# RS232_MAX3223.net
KiCad netlist of a schematic drawn in Altium Designer
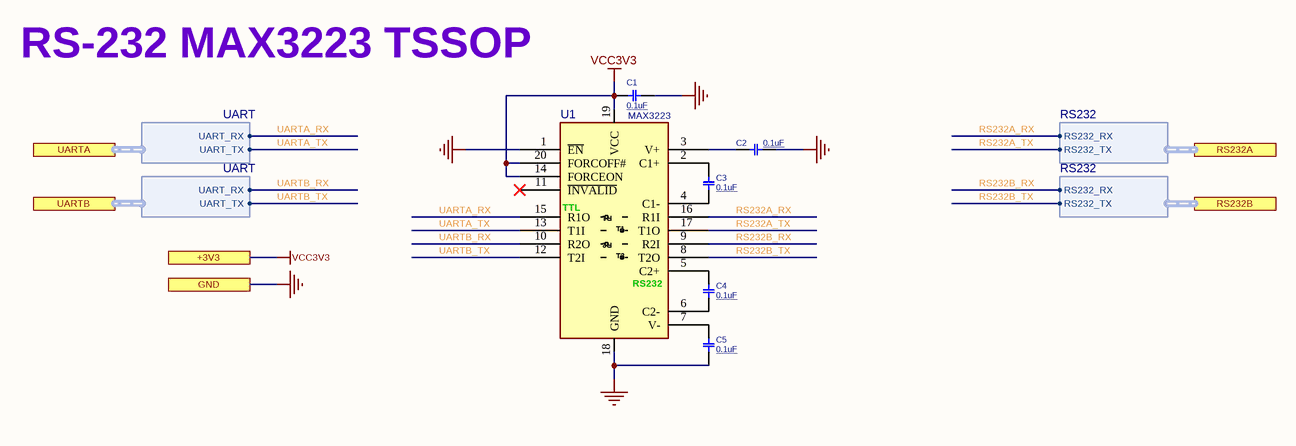
[diagram p0: RS232_MAX3223.SchDoc]

(export (version "E")
  (design (tool "Eeschema 10.0.6"))
  (components
    (comp (ref "C1")
      (value "0.1uF")
      (footprint "C0402")
      (description "CAP, MLCC")
      (fields (field (name "MANF_P#") "MANF_PART#"))
      (libsource (lib "passive_smd") (part "CAP_SMD_MLCC_0402"))
    )
    (comp (ref "C2")
      (value "0.1uF")
      (footprint "C0402")
      (description "CAP, MLCC")
      (fields (field (name "MANF_P#") "MANF_PART#"))
      (libsource (lib "passive_smd") (part "CAP_SMD_MLCC_0402"))
    )
    (comp (ref "C3")
      (value "0.1uF")
      (footprint "C0402")
      (description "CAP, MLCC")
      (fields (field (name "MANF_P#") "MANF_PART#"))
      (libsource (lib "passive_smd") (part "CAP_SMD_MLCC_0402"))
    )
    (comp (ref "C4")
      (value "0.1uF")
      (footprint "C0402")
      (description "CAP, MLCC")
      (fields (field (name "MANF_P#") "MANF_PART#"))
      (libsource (lib "passive_smd") (part "CAP_SMD_MLCC_0402"))
    )
    (comp (ref "C5")
      (value "0.1uF")
      (footprint "C0402")
      (description "CAP, MLCC")
      (fields (field (name "MANF_P#") "MANF_PART#"))
      (libsource (lib "passive_smd") (part "CAP_SMD_MLCC_0402"))
    )
    (comp (ref "U1")
      (value "MAX3223")
      (footprint "SOG65_20_W")
      (description "RS-232, DUAL, +3~5V, Driver/Receiver, Low-Power, up to 1Mbps, Using Four 0.1µF External Capacitor")
      (fields (field (name "MANF") "Maxim Integrated") (field (name "MANF_PART#") "MAX3223ECAP+"))
      (libsource (lib "RASA5") (part "MAX3223_SSOP20W"))
    )
  )
  (nets
    (net (code "3") (name "/RS232A_RX") (class "Default")
      (node (ref "U1") (pin "16") (pinfunction "R1I_16") (pintype "passive"))
    )
    (net (code "4") (name "/RS232A_TX") (class "Default")
      (node (ref "U1") (pin "17") (pinfunction "T1O_17") (pintype "passive"))
    )
    (net (code "5") (name "/RS232B_RX") (class "Default")
      (node (ref "U1") (pin "9") (pinfunction "R2I_9") (pintype "passive"))
    )
    (net (code "6") (name "/RS232B_TX") (class "Default")
      (node (ref "U1") (pin "8") (pinfunction "T2O_8") (pintype "passive"))
    )
    (net (code "7") (name "/UARTA_RX") (class "Default")
      (node (ref "U1") (pin "15") (pinfunction "R1O_15") (pintype "passive"))
    )
    (net (code "8") (name "/UARTA_TX") (class "Default")
      (node (ref "U1") (pin "13") (pinfunction "T1I_13") (pintype "passive"))
    )
    (net (code "9") (name "/UARTB_RX") (class "Default")
      (node (ref "U1") (pin "10") (pinfunction "R2O_10") (pintype "passive"))
    )
    (net (code "10") (name "/UARTB_TX") (class "Default")
      (node (ref "U1") (pin "12") (pinfunction "T2I_12") (pintype "passive"))
    )
    (net (code "13") (name "GND") (class "Default")
      (node (ref "C1") (pin "1") (pinfunction "1_1") (pintype "passive"))
      (node (ref "C2") (pin "2") (pinfunction "2_2") (pintype "passive"))
      (node (ref "C5") (pin "2") (pinfunction "2_2") (pintype "passive"))
      (node (ref "U1") (pin "1") (pinfunction "~{EN}_1") (pintype "passive"))
      (node (ref "U1") (pin "18") (pinfunction "GND_18") (pintype "passive"))
    )
    (net (code "14") (name "Net-(U1-C1+)") (class "Default")
      (node (ref "C3") (pin "1") (pinfunction "1_1") (pintype "passive"))
      (node (ref "U1") (pin "2") (pinfunction "C1+_2") (pintype "passive"))
    )
    (net (code "15") (name "Net-(U1-C1-)") (class "Default")
      (node (ref "C3") (pin "2") (pinfunction "2_2") (pintype "passive"))
      (node (ref "U1") (pin "4") (pinfunction "C1-_4") (pintype "passive"))
    )
    (net (code "16") (name "Net-(U1-C2+)") (class "Default")
      (node (ref "C4") (pin "1") (pinfunction "1_1") (pintype "passive"))
      (node (ref "U1") (pin "5") (pinfunction "C2+_5") (pintype "passive"))
    )
    (net (code "17") (name "Net-(U1-C2-)") (class "Default")
      (node (ref "C4") (pin "2") (pinfunction "2_2") (pintype "passive"))
      (node (ref "U1") (pin "6") (pinfunction "C2-_6") (pintype "passive"))
    )
    (net (code "18") (name "Net-(U1-V+)") (class "Default")
      (node (ref "C2") (pin "1") (pinfunction "1_1") (pintype "passive"))
      (node (ref "U1") (pin "3") (pinfunction "V+_3") (pintype "passive"))
    )
    (net (code "19") (name "Net-(U1-V-)") (class "Default")
      (node (ref "C5") (pin "1") (pinfunction "1_1") (pintype "passive"))
      (node (ref "U1") (pin "7") (pinfunction "V-_7") (pintype "passive"))
    )
    (net (code "20") (name "VCC3V3") (class "Default")
      (node (ref "C1") (pin "2") (pinfunction "2_2") (pintype "passive"))
      (node (ref "U1") (pin "14") (pinfunction "FORCEON_14") (pintype "passive"))
      (node (ref "U1") (pin "19") (pinfunction "VCC_19") (pintype "passive"))
      (node (ref "U1") (pin "20") (pinfunction "FORCOFF#_20") (pintype "passive"))
    )
    (net (code "21") (name "unconnected-(U1-~{INVALID}-Pad11)") (class "Default")
      (node (ref "U1") (pin "11") (pinfunction "~{INVALID}_11") (pintype "passive+no_connect"))
    )
  )
)
